# Analog_Sensors_Sheet.net
KiCad netlist of a schematic drawn in Altium Designer
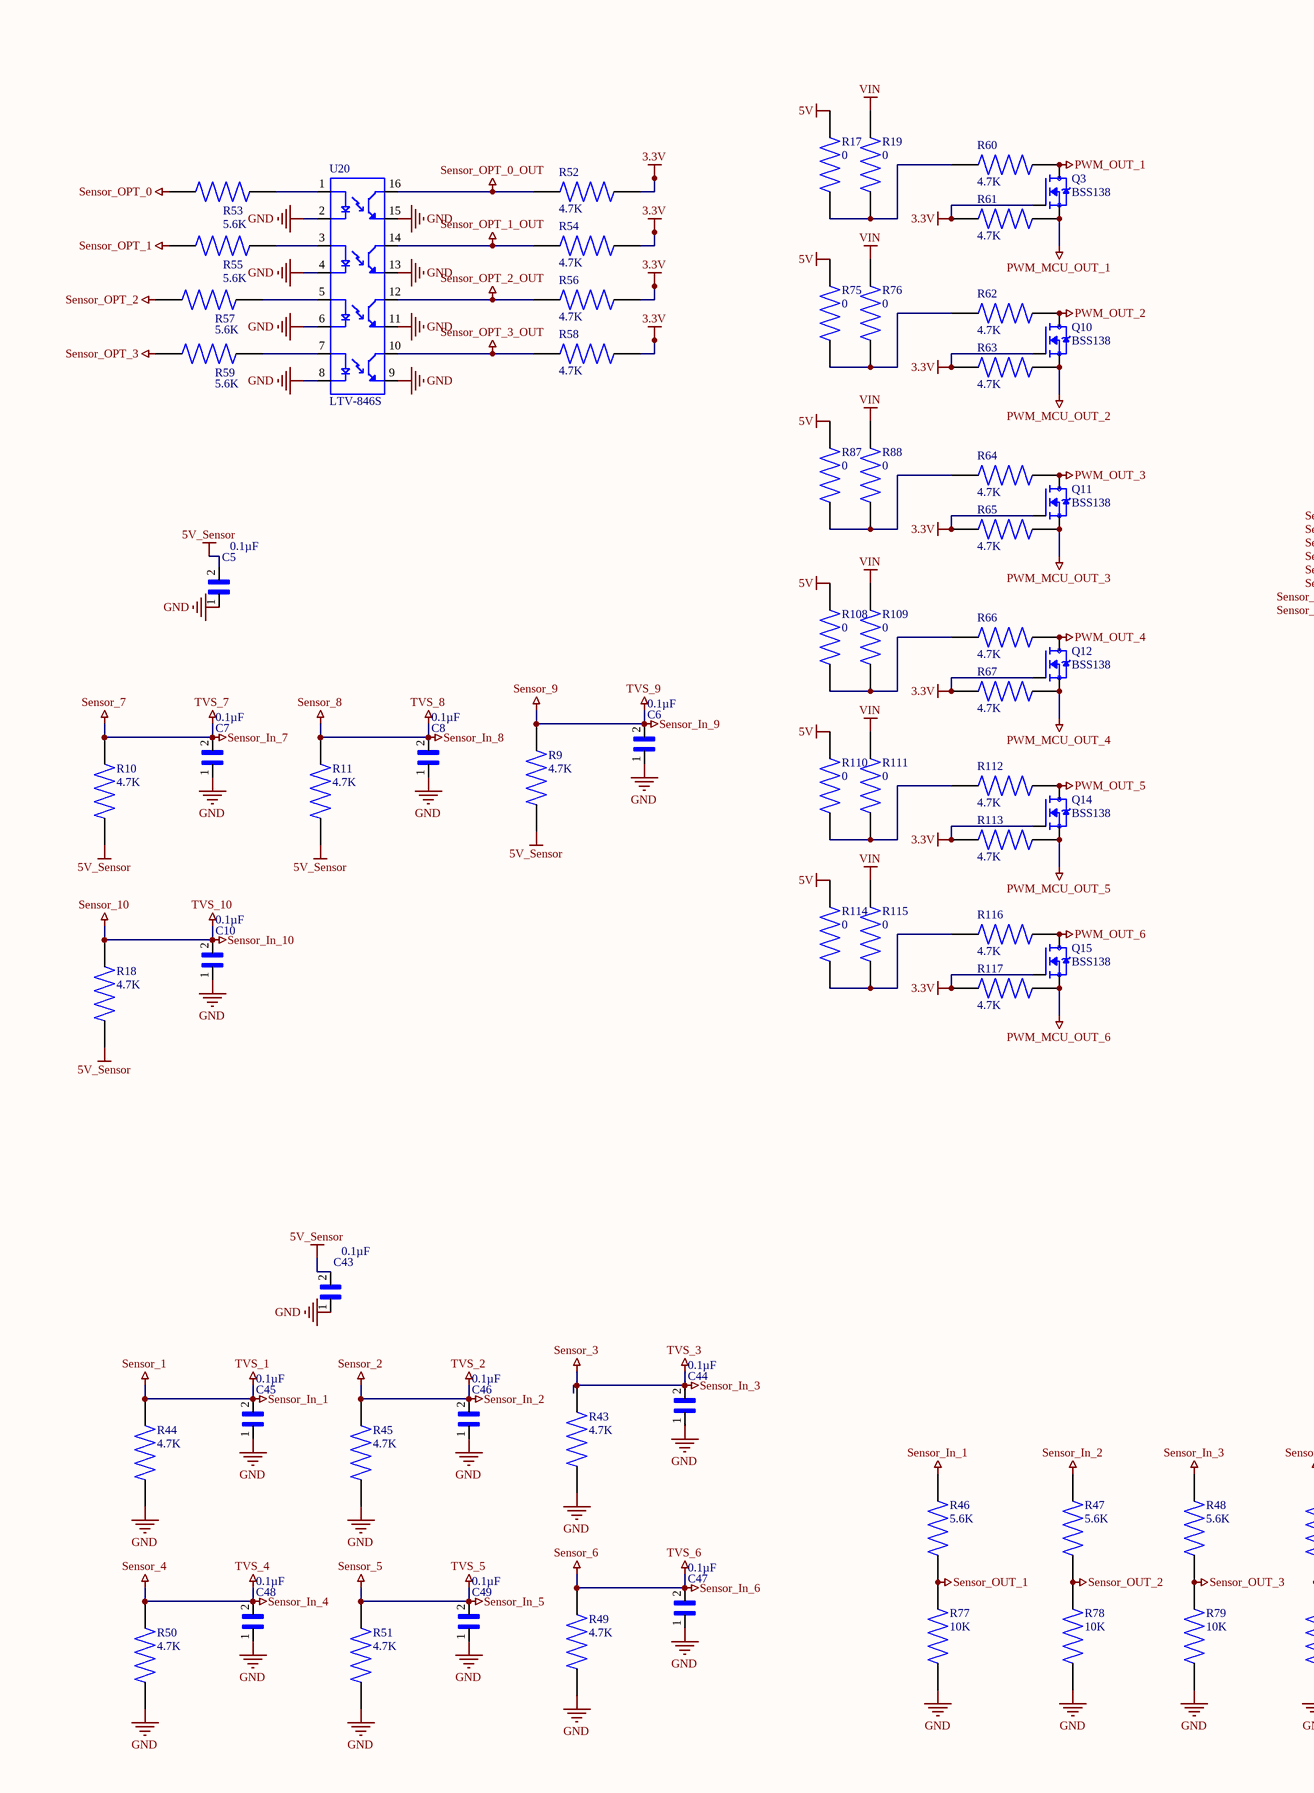
[diagram p0: Analog_Sensors_Sheet.SchDoc, left]
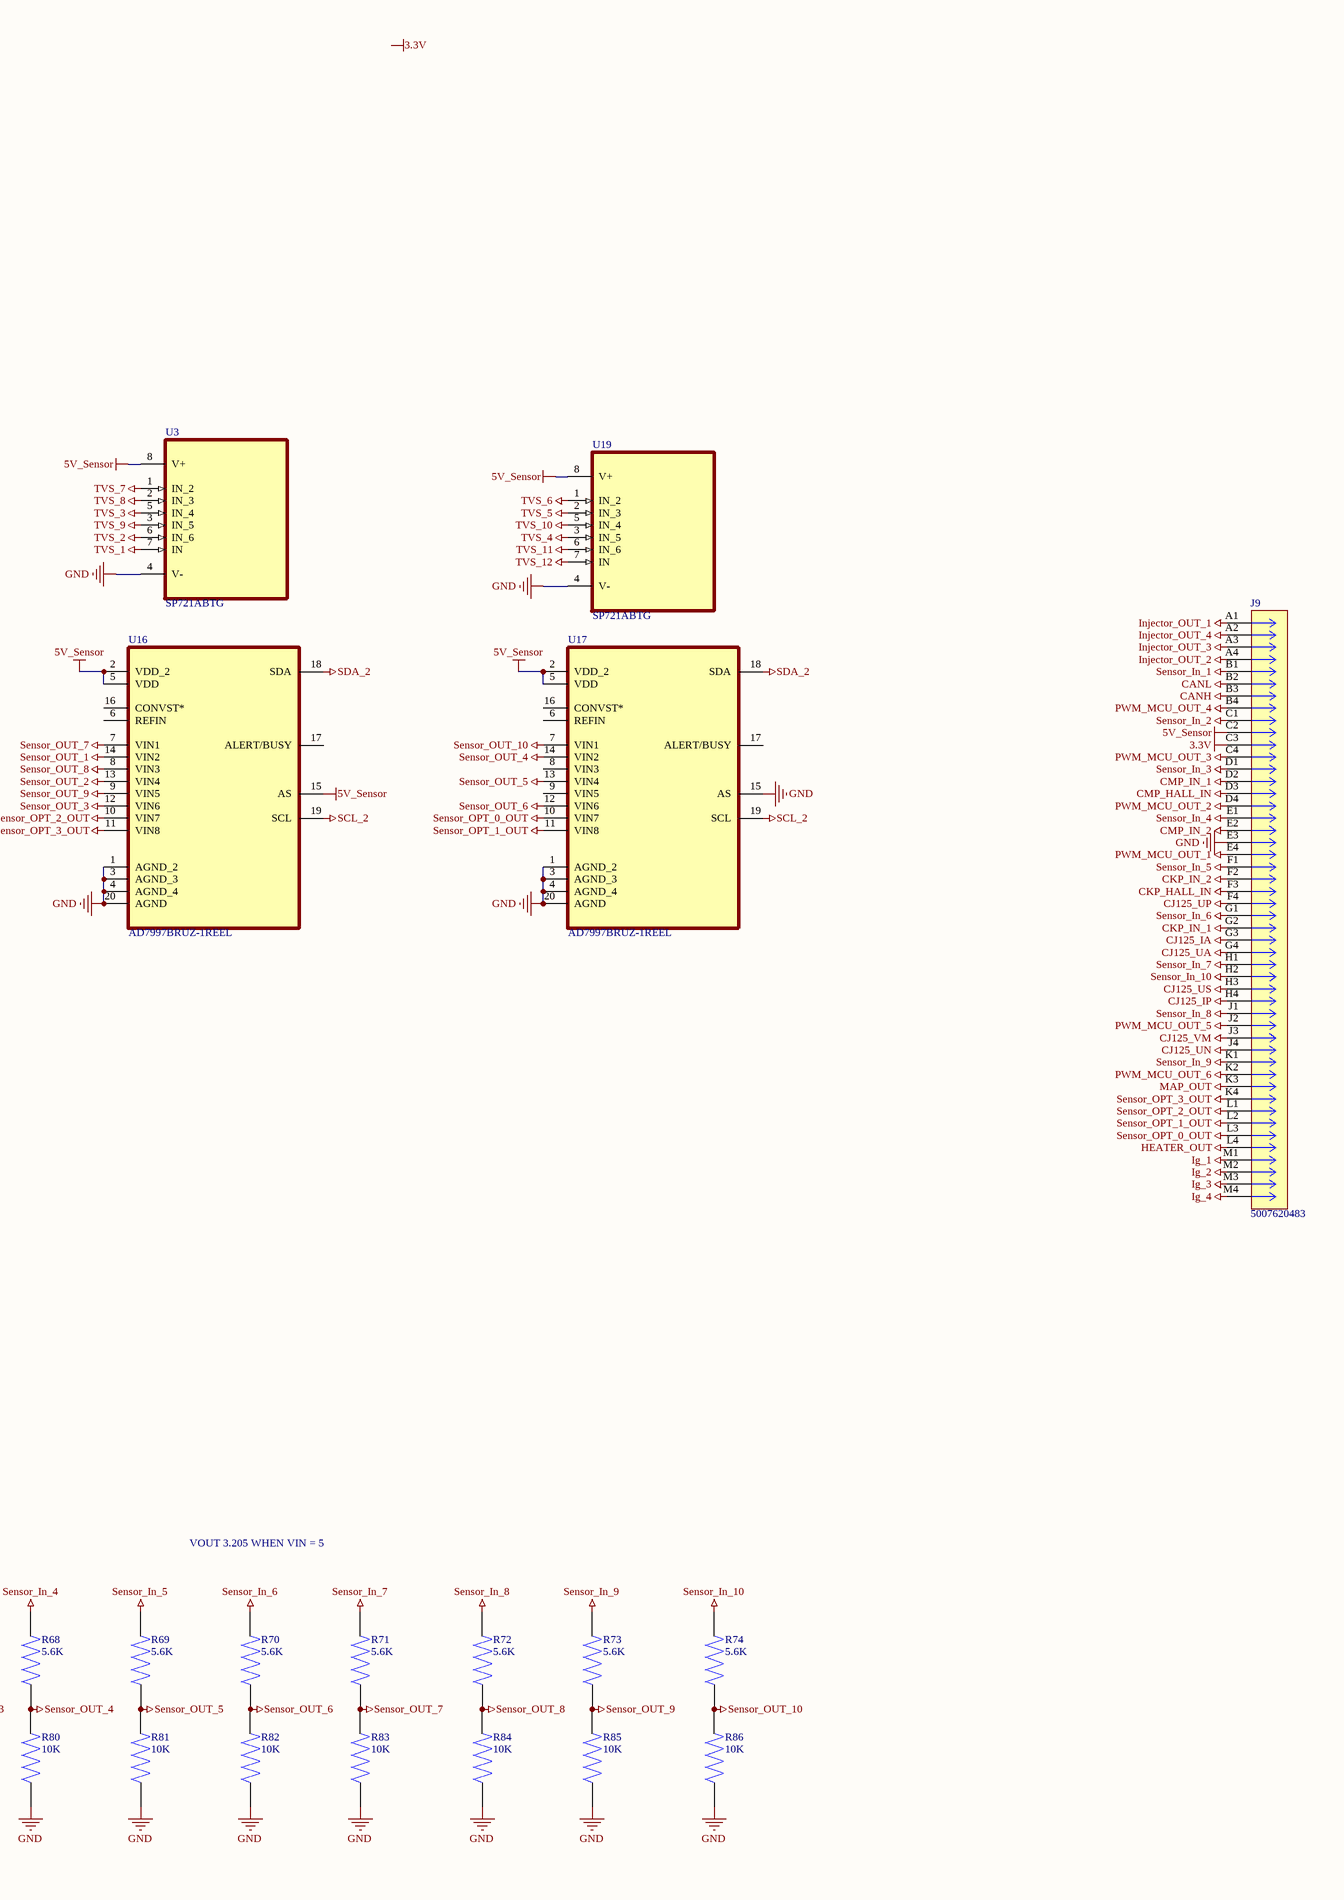
[diagram p1: Analog_Sensors_Sheet.SchDoc, right]

(export (version "E")
  (design (tool "Eeschema 10.0.6"))
  (components
    (comp (ref "C5")
      (value "0.1µF")
      (footprint "CAPC1608X90N")
      (description "Multilayer Ceramic Capacitors MLCC - SMD/SMT")
      (fields (field (name "MP") "06035C104MAZ2A"))
      (libsource (lib "06035C104MAZ2A") (part "06035C104MAZ2A"))
    )
    (comp (ref "C6")
      (value "0.1µF")
      (footprint "CAPC1608X90N")
      (description "Multilayer Ceramic Capacitors MLCC - SMD/SMT")
      (fields (field (name "MP") "06035C104MAZ2A"))
      (libsource (lib "06035C104MAZ2A") (part "06035C104MAZ2A"))
    )
    (comp (ref "C7")
      (value "0.1µF")
      (footprint "CAPC1608X90N")
      (description "Multilayer Ceramic Capacitors MLCC - SMD/SMT")
      (fields (field (name "MP") "06035C104MAZ2A"))
      (libsource (lib "06035C104MAZ2A") (part "06035C104MAZ2A"))
    )
    (comp (ref "C8")
      (value "0.1µF")
      (footprint "CAPC1608X90N")
      (description "Multilayer Ceramic Capacitors MLCC - SMD/SMT")
      (fields (field (name "MP") "06035C104MAZ2A"))
      (libsource (lib "06035C104MAZ2A") (part "06035C104MAZ2A"))
    )
    (comp (ref "C10")
      (value "0.1µF")
      (footprint "CAPC1608X90N")
      (description "Multilayer Ceramic Capacitors MLCC - SMD/SMT")
      (fields (field (name "MP") "06035C104MAZ2A"))
      (libsource (lib "06035C104MAZ2A") (part "06035C104MAZ2A"))
    )
    (comp (ref "C43")
      (value "0.1µF")
      (footprint "CAPC1608X90N")
      (description "Multilayer Ceramic Capacitors MLCC - SMD/SMT")
      (fields (field (name "MP") "06035C104MAZ2A"))
      (libsource (lib "06035C104MAZ2A") (part "06035C104MAZ2A"))
    )
    (comp (ref "C44")
      (value "0.1µF")
      (footprint "CAPC1608X90N")
      (description "Multilayer Ceramic Capacitors MLCC - SMD/SMT")
      (fields (field (name "MP") "06035C104MAZ2A"))
      (libsource (lib "06035C104MAZ2A") (part "06035C104MAZ2A"))
    )
    (comp (ref "C45")
      (value "0.1µF")
      (footprint "CAPC1608X90N")
      (description "Multilayer Ceramic Capacitors MLCC - SMD/SMT")
      (fields (field (name "MP") "06035C104MAZ2A"))
      (libsource (lib "06035C104MAZ2A") (part "06035C104MAZ2A"))
    )
    (comp (ref "C46")
      (value "0.1µF")
      (footprint "CAPC1608X90N")
      (description "Multilayer Ceramic Capacitors MLCC - SMD/SMT")
      (fields (field (name "MP") "06035C104MAZ2A"))
      (libsource (lib "06035C104MAZ2A") (part "06035C104MAZ2A"))
    )
    (comp (ref "C47")
      (value "0.1µF")
      (footprint "CAPC1608X90N")
      (description "Multilayer Ceramic Capacitors MLCC - SMD/SMT")
      (fields (field (name "MP") "06035C104MAZ2A"))
      (libsource (lib "06035C104MAZ2A") (part "06035C104MAZ2A"))
    )
    (comp (ref "C48")
      (value "0.1µF")
      (footprint "CAPC1608X90N")
      (description "Multilayer Ceramic Capacitors MLCC - SMD/SMT")
      (fields (field (name "MP") "06035C104MAZ2A"))
      (libsource (lib "06035C104MAZ2A") (part "06035C104MAZ2A"))
    )
    (comp (ref "C49")
      (value "0.1µF")
      (footprint "CAPC1608X90N")
      (description "Multilayer Ceramic Capacitors MLCC - SMD/SMT")
      (fields (field (name "MP") "06035C104MAZ2A"))
      (libsource (lib "06035C104MAZ2A") (part "06035C104MAZ2A"))
    )
    (comp (ref "J9")
      (value "5007620483")
      (footprint "CONN_SD-500762-001_MOL")
      (libsource (lib "5007620483") (part "5007620483"))
    )
    (comp (ref "Q3")
      (value "BSS138")
      (footprint "SOT95P240X111-3N")
      (description "N-Channel 50 V 220mA (Ta) 350mW (Ta) Surface Mount SOT-23-3")
      (fields (field (name "MF") "onsemi"))
      (libsource (lib "BSS138") (part "BSS138"))
    )
    (comp (ref "Q10")
      (value "BSS138")
      (footprint "SOT95P240X111-3N")
      (description "N-Channel 50 V 220mA (Ta) 350mW (Ta) Surface Mount SOT-23-3")
      (fields (field (name "MF") "onsemi"))
      (libsource (lib "BSS138") (part "BSS138"))
    )
    (comp (ref "Q11")
      (value "BSS138")
      (footprint "SOT95P240X111-3N")
      (description "N-Channel 50 V 220mA (Ta) 350mW (Ta) Surface Mount SOT-23-3")
      (fields (field (name "MF") "onsemi"))
      (libsource (lib "BSS138") (part "BSS138"))
    )
    (comp (ref "Q12")
      (value "BSS138")
      (footprint "SOT95P240X111-3N")
      (description "N-Channel 50 V 220mA (Ta) 350mW (Ta) Surface Mount SOT-23-3")
      (fields (field (name "MF") "onsemi"))
      (libsource (lib "BSS138") (part "BSS138"))
    )
    (comp (ref "Q14")
      (value "BSS138")
      (footprint "SOT95P240X111-3N")
      (description "N-Channel 50 V 220mA (Ta) 350mW (Ta) Surface Mount SOT-23-3")
      (fields (field (name "MF") "onsemi"))
      (libsource (lib "BSS138") (part "BSS138"))
    )
    (comp (ref "Q15")
      (value "BSS138")
      (footprint "SOT95P240X111-3N")
      (description "N-Channel 50 V 220mA (Ta) 350mW (Ta) Surface Mount SOT-23-3")
      (fields (field (name "MF") "onsemi"))
      (libsource (lib "BSS138") (part "BSS138"))
    )
    (comp (ref "R9")
      (value "4.7K")
      (footprint "RESC3116X65N")
      (description "4.7 kOhms Â±1% 0.25W, 1/4W Chip Resistor 1206 (3216 Metric) Moisture Resistant Thick Film")
      (fields (field (name "MF") "Yageo") (field (name "MP") "RC1206FR-074K7L"))
      (libsource (lib "RC1206FR-074K7L") (part "RC1206FR-074K7L"))
    )
    (comp (ref "R10")
      (value "4.7K")
      (footprint "RESC3116X65N")
      (description "4.7 kOhms Â±1% 0.25W, 1/4W Chip Resistor 1206 (3216 Metric) Moisture Resistant Thick Film")
      (fields (field (name "MF") "Yageo") (field (name "MP") "RC1206FR-074K7L"))
      (libsource (lib "RC1206FR-074K7L") (part "RC1206FR-074K7L"))
    )
    (comp (ref "R11")
      (value "4.7K")
      (footprint "RESC3116X65N")
      (description "4.7 kOhms Â±1% 0.25W, 1/4W Chip Resistor 1206 (3216 Metric) Moisture Resistant Thick Film")
      (fields (field (name "MF") "Yageo") (field (name "MP") "RC1206FR-074K7L"))
      (libsource (lib "RC1206FR-074K7L") (part "RC1206FR-074K7L"))
    )
    (comp (ref "R17")
      (value "0")
      (footprint "RESC3116X65N")
      (description "4.7 kOhms Â±1% 0.25W, 1/4W Chip Resistor 1206 (3216 Metric) Moisture Resistant Thick Film")
      (fields (field (name "MF") "Yageo") (field (name "MP") "RC1206FR-074K7L"))
      (libsource (lib "RC1206FR-074K7L") (part "RC1206FR-074K7L"))
    )
    (comp (ref "R18")
      (value "4.7K")
      (footprint "RESC3116X65N")
      (description "4.7 kOhms Â±1% 0.25W, 1/4W Chip Resistor 1206 (3216 Metric) Moisture Resistant Thick Film")
      (fields (field (name "MF") "Yageo") (field (name "MP") "RC1206FR-074K7L"))
      (libsource (lib "RC1206FR-074K7L") (part "RC1206FR-074K7L"))
    )
    (comp (ref "R19")
      (value "0")
      (footprint "RESC3116X65N")
      (description "4.7 kOhms Â±1% 0.25W, 1/4W Chip Resistor 1206 (3216 Metric) Moisture Resistant Thick Film")
      (fields (field (name "MF") "Yageo") (field (name "MP") "RC1206FR-074K7L"))
      (libsource (lib "RC1206FR-074K7L") (part "RC1206FR-074K7L"))
    )
    (comp (ref "R43")
      (value "4.7K")
      (footprint "RESC3116X65N")
      (description "4.7 kOhms Â±1% 0.25W, 1/4W Chip Resistor 1206 (3216 Metric) Moisture Resistant Thick Film")
      (fields (field (name "MF") "Yageo") (field (name "MP") "RC1206FR-074K7L"))
      (libsource (lib "RC1206FR-074K7L") (part "RC1206FR-074K7L"))
    )
    (comp (ref "R44")
      (value "4.7K")
      (footprint "RESC3116X65N")
      (description "4.7 kOhms Â±1% 0.25W, 1/4W Chip Resistor 1206 (3216 Metric) Moisture Resistant Thick Film")
      (fields (field (name "MF") "Yageo") (field (name "MP") "RC1206FR-074K7L"))
      (libsource (lib "RC1206FR-074K7L") (part "RC1206FR-074K7L"))
    )
    (comp (ref "R45")
      (value "4.7K")
      (footprint "RESC3116X65N")
      (description "4.7 kOhms Â±1% 0.25W, 1/4W Chip Resistor 1206 (3216 Metric) Moisture Resistant Thick Film")
      (fields (field (name "MF") "Yageo") (field (name "MP") "RC1206FR-074K7L"))
      (libsource (lib "RC1206FR-074K7L") (part "RC1206FR-074K7L"))
    )
    (comp (ref "R46")
      (value "5.6K")
      (footprint "RESC3116X65N")
      (fields (field (name "MP") "AA1206JR-07470RL"))
      (libsource (lib "AA1206JR-07470RL") (part "AA1206JR-07470RL"))
    )
    (comp (ref "R47")
      (value "5.6K")
      (footprint "RESC3116X65N")
      (fields (field (name "MP") "AA1206JR-07470RL"))
      (libsource (lib "AA1206JR-07470RL") (part "AA1206JR-07470RL"))
    )
    (comp (ref "R48")
      (value "5.6K")
      (footprint "RESC3116X65N")
      (fields (field (name "MP") "AA1206JR-07470RL"))
      (libsource (lib "AA1206JR-07470RL") (part "AA1206JR-07470RL"))
    )
    (comp (ref "R49")
      (value "4.7K")
      (footprint "RESC3116X65N")
      (description "4.7 kOhms Â±1% 0.25W, 1/4W Chip Resistor 1206 (3216 Metric) Moisture Resistant Thick Film")
      (fields (field (name "MF") "Yageo") (field (name "MP") "RC1206FR-074K7L"))
      (libsource (lib "RC1206FR-074K7L") (part "RC1206FR-074K7L"))
    )
    (comp (ref "R50")
      (value "4.7K")
      (footprint "RESC3116X65N")
      (description "4.7 kOhms Â±1% 0.25W, 1/4W Chip Resistor 1206 (3216 Metric) Moisture Resistant Thick Film")
      (fields (field (name "MF") "Yageo") (field (name "MP") "RC1206FR-074K7L"))
      (libsource (lib "RC1206FR-074K7L") (part "RC1206FR-074K7L"))
    )
    (comp (ref "R51")
      (value "4.7K")
      (footprint "RESC3116X65N")
      (description "4.7 kOhms Â±1% 0.25W, 1/4W Chip Resistor 1206 (3216 Metric) Moisture Resistant Thick Film")
      (fields (field (name "MF") "Yageo") (field (name "MP") "RC1206FR-074K7L"))
      (libsource (lib "RC1206FR-074K7L") (part "RC1206FR-074K7L"))
    )
    (comp (ref "R52")
      (value "4.7K")
      (footprint "RES_ERJS06J472V")
      (fields (field (name "MP") "ERJS06J472V"))
      (libsource (lib "ERJS06J472V") (part "ERJS06J472V"))
    )
    (comp (ref "R53")
      (value "5.6K")
      (footprint "RESC3216X70N")
      (description "Res Thick Film 1206 220 Ohm 1% 0.25W(1/4W) ?100ppm/?C SMD Automotive T/R")
      (fields (field (name "MP") "RK73H2BTTD2200F"))
      (libsource (lib "RK73H2BTTD2200F") (part "RK73H2BTTD2200F"))
    )
    (comp (ref "R54")
      (value "4.7K")
      (footprint "RES_ERJS06J472V")
      (fields (field (name "MP") "ERJS06J472V"))
      (libsource (lib "ERJS06J472V") (part "ERJS06J472V"))
    )
    (comp (ref "R55")
      (value "5.6K")
      (footprint "RESC3216X70N")
      (description "Res Thick Film 1206 220 Ohm 1% 0.25W(1/4W) ?100ppm/?C SMD Automotive T/R")
      (fields (field (name "MP") "RK73H2BTTD2200F"))
      (libsource (lib "RK73H2BTTD2200F") (part "RK73H2BTTD2200F"))
    )
    (comp (ref "R56")
      (value "4.7K")
      (footprint "RES_ERJS06J472V")
      (fields (field (name "MP") "ERJS06J472V"))
      (libsource (lib "ERJS06J472V") (part "ERJS06J472V"))
    )
    (comp (ref "R57")
      (value "5.6K")
      (footprint "RESC3216X70N")
      (description "Res Thick Film 1206 220 Ohm 1% 0.25W(1/4W) ?100ppm/?C SMD Automotive T/R")
      (fields (field (name "MP") "RK73H2BTTD2200F"))
      (libsource (lib "RK73H2BTTD2200F") (part "RK73H2BTTD2200F"))
    )
    (comp (ref "R58")
      (value "4.7K")
      (footprint "RES_ERJS06J472V")
      (fields (field (name "MP") "ERJS06J472V"))
      (libsource (lib "ERJS06J472V") (part "ERJS06J472V"))
    )
    (comp (ref "R59")
      (value "5.6K")
      (footprint "RESC3216X70N")
      (description "Res Thick Film 1206 220 Ohm 1% 0.25W(1/4W) ?100ppm/?C SMD Automotive T/R")
      (fields (field (name "MP") "RK73H2BTTD2200F"))
      (libsource (lib "RK73H2BTTD2200F") (part "RK73H2BTTD2200F"))
    )
    (comp (ref "R60")
      (value "4.7K")
      (footprint "RESC3116X65N")
      (description "4.7 kOhms Â±1% 0.25W, 1/4W Chip Resistor 1206 (3216 Metric) Moisture Resistant Thick Film")
      (fields (field (name "MF") "Yageo") (field (name "MP") "RC1206FR-074K7L"))
      (libsource (lib "RC1206FR-074K7L") (part "RC1206FR-074K7L"))
    )
    (comp (ref "R61")
      (value "4.7K")
      (footprint "RESC3116X65N")
      (description "4.7 kOhms Â±1% 0.25W, 1/4W Chip Resistor 1206 (3216 Metric) Moisture Resistant Thick Film")
      (fields (field (name "MF") "Yageo") (field (name "MP") "RC1206FR-074K7L"))
      (libsource (lib "RC1206FR-074K7L") (part "RC1206FR-074K7L"))
    )
    (comp (ref "R62")
      (value "4.7K")
      (footprint "RESC3116X65N")
      (description "4.7 kOhms Â±1% 0.25W, 1/4W Chip Resistor 1206 (3216 Metric) Moisture Resistant Thick Film")
      (fields (field (name "MF") "Yageo") (field (name "MP") "RC1206FR-074K7L"))
      (libsource (lib "RC1206FR-074K7L") (part "RC1206FR-074K7L"))
    )
    (comp (ref "R63")
      (value "4.7K")
      (footprint "RESC3116X65N")
      (description "4.7 kOhms Â±1% 0.25W, 1/4W Chip Resistor 1206 (3216 Metric) Moisture Resistant Thick Film")
      (fields (field (name "MF") "Yageo") (field (name "MP") "RC1206FR-074K7L"))
      (libsource (lib "RC1206FR-074K7L") (part "RC1206FR-074K7L"))
    )
    (comp (ref "R64")
      (value "4.7K")
      (footprint "RESC3116X65N")
      (description "4.7 kOhms Â±1% 0.25W, 1/4W Chip Resistor 1206 (3216 Metric) Moisture Resistant Thick Film")
      (fields (field (name "MF") "Yageo") (field (name "MP") "RC1206FR-074K7L"))
      (libsource (lib "RC1206FR-074K7L") (part "RC1206FR-074K7L"))
    )
    (comp (ref "R65")
      (value "4.7K")
      (footprint "RESC3116X65N")
      (description "4.7 kOhms Â±1% 0.25W, 1/4W Chip Resistor 1206 (3216 Metric) Moisture Resistant Thick Film")
      (fields (field (name "MF") "Yageo") (field (name "MP") "RC1206FR-074K7L"))
      (libsource (lib "RC1206FR-074K7L") (part "RC1206FR-074K7L"))
    )
    (comp (ref "R66")
      (value "4.7K")
      (footprint "RESC3116X65N")
      (description "4.7 kOhms Â±1% 0.25W, 1/4W Chip Resistor 1206 (3216 Metric) Moisture Resistant Thick Film")
      (fields (field (name "MF") "Yageo") (field (name "MP") "RC1206FR-074K7L"))
      (libsource (lib "RC1206FR-074K7L") (part "RC1206FR-074K7L"))
    )
    (comp (ref "R67")
      (value "4.7K")
      (footprint "RESC3116X65N")
      (description "4.7 kOhms Â±1% 0.25W, 1/4W Chip Resistor 1206 (3216 Metric) Moisture Resistant Thick Film")
      (fields (field (name "MF") "Yageo") (field (name "MP") "RC1206FR-074K7L"))
      (libsource (lib "RC1206FR-074K7L") (part "RC1206FR-074K7L"))
    )
    (comp (ref "R68")
      (value "5.6K")
      (footprint "RESC3116X65N")
      (fields (field (name "MP") "AA1206JR-07470RL"))
      (libsource (lib "AA1206JR-07470RL") (part "AA1206JR-07470RL"))
    )
    (comp (ref "R69")
      (value "5.6K")
      (footprint "RESC3116X65N")
      (fields (field (name "MP") "AA1206JR-07470RL"))
      (libsource (lib "AA1206JR-07470RL") (part "AA1206JR-07470RL"))
    )
    (comp (ref "R70")
      (value "5.6K")
      (footprint "RESC3116X65N")
      (fields (field (name "MP") "AA1206JR-07470RL"))
      (libsource (lib "AA1206JR-07470RL") (part "AA1206JR-07470RL"))
    )
    (comp (ref "R71")
      (value "5.6K")
      (footprint "RESC3116X65N")
      (fields (field (name "MP") "AA1206JR-07470RL"))
      (libsource (lib "AA1206JR-07470RL") (part "AA1206JR-07470RL"))
    )
    (comp (ref "R72")
      (value "5.6K")
      (footprint "RESC3116X65N")
      (fields (field (name "MP") "AA1206JR-07470RL"))
      (libsource (lib "AA1206JR-07470RL") (part "AA1206JR-07470RL"))
    )
    (comp (ref "R73")
      (value "5.6K")
      (footprint "RESC3116X65N")
      (fields (field (name "MP") "AA1206JR-07470RL"))
      (libsource (lib "AA1206JR-07470RL") (part "AA1206JR-07470RL"))
    )
    (comp (ref "R74")
      (value "5.6K")
      (footprint "RESC3116X65N")
      (fields (field (name "MP") "AA1206JR-07470RL"))
      (libsource (lib "AA1206JR-07470RL") (part "AA1206JR-07470RL"))
    )
    (comp (ref "R75")
      (value "0")
      (footprint "RESC3116X65N")
      (description "4.7 kOhms Â±1% 0.25W, 1/4W Chip Resistor 1206 (3216 Metric) Moisture Resistant Thick Film")
      (fields (field (name "MF") "Yageo") (field (name "MP") "RC1206FR-074K7L"))
      (libsource (lib "RC1206FR-074K7L") (part "RC1206FR-074K7L"))
    )
    (comp (ref "R76")
      (value "0")
      (footprint "RESC3116X65N")
      (description "4.7 kOhms Â±1% 0.25W, 1/4W Chip Resistor 1206 (3216 Metric) Moisture Resistant Thick Film")
      (fields (field (name "MF") "Yageo") (field (name "MP") "RC1206FR-074K7L"))
      (libsource (lib "RC1206FR-074K7L") (part "RC1206FR-074K7L"))
    )
    (comp (ref "R77")
      (value "10K")
      (footprint "RESC3116X65N")
      (fields (field (name "MP") "AA1206JR-07470RL"))
      (libsource (lib "AA1206JR-07470RL") (part "AA1206JR-07470RL"))
    )
    (comp (ref "R78")
      (value "10K")
      (footprint "RESC3116X65N")
      (fields (field (name "MP") "AA1206JR-07470RL"))
      (libsource (lib "AA1206JR-07470RL") (part "AA1206JR-07470RL"))
    )
    (comp (ref "R79")
      (value "10K")
      (footprint "RESC3116X65N")
      (fields (field (name "MP") "AA1206JR-07470RL"))
      (libsource (lib "AA1206JR-07470RL") (part "AA1206JR-07470RL"))
    )
    (comp (ref "R80")
      (value "10K")
      (footprint "RESC3116X65N")
      (fields (field (name "MP") "AA1206JR-07470RL"))
      (libsource (lib "AA1206JR-07470RL") (part "AA1206JR-07470RL"))
    )
    (comp (ref "R81")
      (value "10K")
      (footprint "RESC3116X65N")
      (fields (field (name "MP") "AA1206JR-07470RL"))
      (libsource (lib "AA1206JR-07470RL") (part "AA1206JR-07470RL"))
    )
    (comp (ref "R82")
      (value "10K")
      (footprint "RESC3116X65N")
      (fields (field (name "MP") "AA1206JR-07470RL"))
      (libsource (lib "AA1206JR-07470RL") (part "AA1206JR-07470RL"))
    )
    (comp (ref "R83")
      (value "10K")
      (footprint "RESC3116X65N")
      (fields (field (name "MP") "AA1206JR-07470RL"))
      (libsource (lib "AA1206JR-07470RL") (part "AA1206JR-07470RL"))
    )
    (comp (ref "R84")
      (value "10K")
      (footprint "RESC3116X65N")
      (fields (field (name "MP") "AA1206JR-07470RL"))
      (libsource (lib "AA1206JR-07470RL") (part "AA1206JR-07470RL"))
    )
    (comp (ref "R85")
      (value "10K")
      (footprint "RESC3116X65N")
      (fields (field (name "MP") "AA1206JR-07470RL"))
      (libsource (lib "AA1206JR-07470RL") (part "AA1206JR-07470RL"))
    )
    (comp (ref "R86")
      (value "10K")
      (footprint "RESC3116X65N")
      (fields (field (name "MP") "AA1206JR-07470RL"))
      (libsource (lib "AA1206JR-07470RL") (part "AA1206JR-07470RL"))
    )
    (comp (ref "R87")
      (value "0")
      (footprint "RESC3116X65N")
      (description "4.7 kOhms Â±1% 0.25W, 1/4W Chip Resistor 1206 (3216 Metric) Moisture Resistant Thick Film")
      (fields (field (name "MF") "Yageo") (field (name "MP") "RC1206FR-074K7L"))
      (libsource (lib "RC1206FR-074K7L") (part "RC1206FR-074K7L"))
    )
    (comp (ref "R88")
      (value "0")
      (footprint "RESC3116X65N")
      (description "4.7 kOhms Â±1% 0.25W, 1/4W Chip Resistor 1206 (3216 Metric) Moisture Resistant Thick Film")
      (fields (field (name "MF") "Yageo") (field (name "MP") "RC1206FR-074K7L"))
      (libsource (lib "RC1206FR-074K7L") (part "RC1206FR-074K7L"))
    )
    (comp (ref "R108")
      (value "0")
      (footprint "RESC3116X65N")
      (description "4.7 kOhms Â±1% 0.25W, 1/4W Chip Resistor 1206 (3216 Metric) Moisture Resistant Thick Film")
      (fields (field (name "MF") "Yageo") (field (name "MP") "RC1206FR-074K7L"))
      (libsource (lib "RC1206FR-074K7L") (part "RC1206FR-074K7L"))
    )
    (comp (ref "R109")
      (value "0")
      (footprint "RESC3116X65N")
      (description "4.7 kOhms Â±1% 0.25W, 1/4W Chip Resistor 1206 (3216 Metric) Moisture Resistant Thick Film")
      (fields (field (name "MF") "Yageo") (field (name "MP") "RC1206FR-074K7L"))
      (libsource (lib "RC1206FR-074K7L") (part "RC1206FR-074K7L"))
    )
    (comp (ref "R110")
      (value "0")
      (footprint "RESC3116X65N")
      (description "4.7 kOhms Â±1% 0.25W, 1/4W Chip Resistor 1206 (3216 Metric) Moisture Resistant Thick Film")
      (fields (field (name "MF") "Yageo") (field (name "MP") "RC1206FR-074K7L"))
      (libsource (lib "RC1206FR-074K7L") (part "RC1206FR-074K7L"))
    )
    (comp (ref "R111")
      (value "0")
      (footprint "RESC3116X65N")
      (description "4.7 kOhms Â±1% 0.25W, 1/4W Chip Resistor 1206 (3216 Metric) Moisture Resistant Thick Film")
      (fields (field (name "MF") "Yageo") (field (name "MP") "RC1206FR-074K7L"))
      (libsource (lib "RC1206FR-074K7L") (part "RC1206FR-074K7L"))
    )
    (comp (ref "R112")
      (value "4.7K")
      (footprint "RESC3116X65N")
      (description "4.7 kOhms Â±1% 0.25W, 1/4W Chip Resistor 1206 (3216 Metric) Moisture Resistant Thick Film")
      (fields (field (name "MF") "Yageo") (field (name "MP") "RC1206FR-074K7L"))
      (libsource (lib "RC1206FR-074K7L") (part "RC1206FR-074K7L"))
    )
    (comp (ref "R113")
      (value "4.7K")
      (footprint "RESC3116X65N")
      (description "4.7 kOhms Â±1% 0.25W, 1/4W Chip Resistor 1206 (3216 Metric) Moisture Resistant Thick Film")
      (fields (field (name "MF") "Yageo") (field (name "MP") "RC1206FR-074K7L"))
      (libsource (lib "RC1206FR-074K7L") (part "RC1206FR-074K7L"))
    )
    (comp (ref "R114")
      (value "0")
      (footprint "RESC3116X65N")
      (description "4.7 kOhms Â±1% 0.25W, 1/4W Chip Resistor 1206 (3216 Metric) Moisture Resistant Thick Film")
      (fields (field (name "MF") "Yageo") (field (name "MP") "RC1206FR-074K7L"))
      (libsource (lib "RC1206FR-074K7L") (part "RC1206FR-074K7L"))
    )
    (comp (ref "R115")
      (value "0")
      (footprint "RESC3116X65N")
      (description "4.7 kOhms Â±1% 0.25W, 1/4W Chip Resistor 1206 (3216 Metric) Moisture Resistant Thick Film")
      (fields (field (name "MF") "Yageo") (field (name "MP") "RC1206FR-074K7L"))
      (libsource (lib "RC1206FR-074K7L") (part "RC1206FR-074K7L"))
    )
    (comp (ref "R116")
      (value "4.7K")
      (footprint "RESC3116X65N")
      (description "4.7 kOhms Â±1% 0.25W, 1/4W Chip Resistor 1206 (3216 Metric) Moisture Resistant Thick Film")
      (fields (field (name "MF") "Yageo") (field (name "MP") "RC1206FR-074K7L"))
      (libsource (lib "RC1206FR-074K7L") (part "RC1206FR-074K7L"))
    )
    (comp (ref "R117")
      (value "4.7K")
      (footprint "RESC3116X65N")
      (description "4.7 kOhms Â±1% 0.25W, 1/4W Chip Resistor 1206 (3216 Metric) Moisture Resistant Thick Film")
      (fields (field (name "MF") "Yageo") (field (name "MP") "RC1206FR-074K7L"))
      (libsource (lib "RC1206FR-074K7L") (part "RC1206FR-074K7L"))
    )
    (comp (ref "U3")
      (value "SP721ABTG")
      (footprint "SOIC127P600X175-8N")
      (description "TVS Diode Arrays")
      (libsource (lib "SP721ABTG") (part "SP721ABTG"))
    )
    (comp (ref "U16")
      (value "AD7997BRUZ-1REEL")
      (footprint "SOP65P640X120-20N")
      (fields (field (name "MF") "Analog Devices") (field (name "MP") "AD7997BRUZ1"))
      (libsource (lib "AD7997BRUZ-1REEL") (part "AD7997BRUZ-1REEL"))
    )
    (comp (ref "U17")
      (value "AD7997BRUZ-1REEL")
      (footprint "SOP65P640X120-20N")
      (fields (field (name "MF") "Analog Devices") (field (name "MP") "AD7997BRUZ1"))
      (libsource (lib "AD7997BRUZ-1REEL") (part "AD7997BRUZ-1REEL"))
    )
    (comp (ref "U19")
      (value "SP721ABTG")
      (footprint "SOIC127P600X175-8N")
      (description "TVS Diode Arrays")
      (libsource (lib "SP721ABTG") (part "SP721ABTG"))
    )
    (comp (ref "U20")
      (value "LTV-846S")
      (footprint "SOIC254P1016X460-16N")
      (description "Optoisolator Transistor Output 5000Vrms 4 Channel 16-SMD")
      (fields (field (name "MF") "Lite-On Inc.") (field (name "DIGI-KEY_PART_NUMBER") "160-1365-5-ND"))
      (libsource (lib "LTV-846S") (part "LTV-846S"))
    )
  )
  (nets
    (net (code "1") (name "3.3V") (class "Default")
      (node (ref "J9") (pin "C3") (pinfunction "C3_C3") (pintype "passive"))
      (node (ref "Q10") (pin "1") (pinfunction "G_1") (pintype "passive"))
      (node (ref "Q11") (pin "1") (pinfunction "G_1") (pintype "passive"))
      (node (ref "Q12") (pin "1") (pinfunction "G_1") (pintype "passive"))
      (node (ref "Q14") (pin "1") (pinfunction "G_1") (pintype "passive"))
      (node (ref "Q15") (pin "1") (pinfunction "G_1") (pintype "passive"))
      (node (ref "Q3") (pin "1") (pinfunction "G_1") (pintype "passive"))
      (node (ref "R113") (pin "2") (pinfunction "2_2") (pintype "passive"))
      (node (ref "R117") (pin "2") (pinfunction "2_2") (pintype "passive"))
      (node (ref "R52") (pin "2") (pinfunction "2_2") (pintype "passive"))
      (node (ref "R54") (pin "2") (pinfunction "2_2") (pintype "passive"))
      (node (ref "R56") (pin "2") (pinfunction "2_2") (pintype "passive"))
      (node (ref "R58") (pin "2") (pinfunction "2_2") (pintype "passive"))
      (node (ref "R61") (pin "2") (pinfunction "2_2") (pintype "passive"))
      (node (ref "R63") (pin "2") (pinfunction "2_2") (pintype "passive"))
      (node (ref "R65") (pin "2") (pinfunction "2_2") (pintype "passive"))
      (node (ref "R67") (pin "2") (pinfunction "2_2") (pintype "passive"))
    )
    (net (code "2") (name "5V") (class "Default")
      (node (ref "R108") (pin "2") (pinfunction "2_2") (pintype "passive"))
      (node (ref "R110") (pin "2") (pinfunction "2_2") (pintype "passive"))
      (node (ref "R114") (pin "2") (pinfunction "2_2") (pintype "passive"))
      (node (ref "R17") (pin "2") (pinfunction "2_2") (pintype "passive"))
      (node (ref "R75") (pin "2") (pinfunction "2_2") (pintype "passive"))
      (node (ref "R87") (pin "2") (pinfunction "2_2") (pintype "passive"))
    )
    (net (code "3") (name "5V_Sensor") (class "Default")
      (node (ref "C43") (pin "2") (pinfunction "2_2") (pintype "passive"))
      (node (ref "C5") (pin "2") (pinfunction "2_2") (pintype "passive"))
      (node (ref "J9") (pin "C2") (pinfunction "C2_C2") (pintype "passive"))
      (node (ref "R10") (pin "1") (pinfunction "1_1") (pintype "passive"))
      (node (ref "R11") (pin "1") (pinfunction "1_1") (pintype "passive"))
      (node (ref "R18") (pin "1") (pinfunction "1_1") (pintype "passive"))
      (node (ref "R9") (pin "1") (pinfunction "1_1") (pintype "passive"))
      (node (ref "U16") (pin "15") (pinfunction "AS_15") (pintype "passive"))
      (node (ref "U16") (pin "2") (pinfunction "VDD_2_2") (pintype "power_in"))
      (node (ref "U16") (pin "5") (pinfunction "VDD_5") (pintype "power_in"))
      (node (ref "U17") (pin "2") (pinfunction "VDD_2_2") (pintype "power_in"))
      (node (ref "U17") (pin "5") (pinfunction "VDD_5") (pintype "power_in"))
      (node (ref "U19") (pin "8") (pinfunction "V+_8") (pintype "power_in"))
      (node (ref "U3") (pin "8") (pinfunction "V+_8") (pintype "power_in"))
    )
    (net (code "4") (name "CANH") (class "Default")
      (node (ref "J9") (pin "B3") (pinfunction "B3_B3") (pintype "passive"))
    )
    (net (code "5") (name "CANL") (class "Default")
      (node (ref "J9") (pin "B2") (pinfunction "B2_B2") (pintype "passive"))
    )
    (net (code "6") (name "CJ125_IA") (class "Default")
      (node (ref "J9") (pin "G3") (pinfunction "G3_G3") (pintype "passive"))
    )
    (net (code "7") (name "CJ125_IP") (class "Default")
      (node (ref "J9") (pin "H4") (pinfunction "H4_H4") (pintype "passive"))
    )
    (net (code "8") (name "CJ125_UA") (class "Default")
      (node (ref "J9") (pin "G4") (pinfunction "G4_G4") (pintype "passive"))
    )
    (net (code "9") (name "CJ125_UN") (class "Default")
      (node (ref "J9") (pin "J4") (pinfunction "J4_J4") (pintype "passive"))
    )
    (net (code "10") (name "CJ125_UP") (class "Default")
      (node (ref "J9") (pin "F4") (pinfunction "F4_F4") (pintype "passive"))
    )
    (net (code "11") (name "CJ125_US") (class "Default")
      (node (ref "J9") (pin "H3") (pinfunction "H3_H3") (pintype "passive"))
    )
    (net (code "12") (name "CJ125_VM") (class "Default")
      (node (ref "J9") (pin "J3") (pinfunction "J3_J3") (pintype "passive"))
    )
    (net (code "13") (name "CKP_HALL_IN") (class "Default")
      (node (ref "J9") (pin "F3") (pinfunction "F3_F3") (pintype "passive"))
    )
    (net (code "14") (name "CKP_IN_1") (class "Default")
      (node (ref "J9") (pin "G2") (pinfunction "G2_G2") (pintype "passive"))
    )
    (net (code "15") (name "CKP_IN_2") (class "Default")
      (node (ref "J9") (pin "F2") (pinfunction "F2_F2") (pintype "passive"))
    )
    (net (code "16") (name "CMP_HALL_IN") (class "Default")
      (node (ref "J9") (pin "D3") (pinfunction "D3_D3") (pintype "passive"))
    )
    (net (code "17") (name "CMP_IN_1") (class "Default")
      (node (ref "J9") (pin "D2") (pinfunction "D2_D2") (pintype "passive"))
    )
    (net (code "18") (name "CMP_IN_2") (class "Default")
      (node (ref "J9") (pin "E2") (pinfunction "E2_E2") (pintype "passive"))
    )
    (net (code "19") (name "GND") (class "Default")
      (node (ref "C10") (pin "1") (pinfunction "1_1") (pintype "passive"))
      (node (ref "C43") (pin "1") (pinfunction "1_1") (pintype "passive"))
      (node (ref "C44") (pin "1") (pinfunction "1_1") (pintype "passive"))
      (node (ref "C45") (pin "1") (pinfunction "1_1") (pintype "passive"))
      (node (ref "C46") (pin "1") (pinfunction "1_1") (pintype "passive"))
      (node (ref "C47") (pin "1") (pinfunction "1_1") (pintype "passive"))
      (node (ref "C48") (pin "1") (pinfunction "1_1") (pintype "passive"))
      (node (ref "C49") (pin "1") (pinfunction "1_1") (pintype "passive"))
      (node (ref "C5") (pin "1") (pinfunction "1_1") (pintype "passive"))
      (node (ref "C6") (pin "1") (pinfunction "1_1") (pintype "passive"))
      (node (ref "C7") (pin "1") (pinfunction "1_1") (pintype "passive"))
      (node (ref "C8") (pin "1") (pinfunction "1_1") (pintype "passive"))
      (node (ref "J9") (pin "E3") (pinfunction "E3_E3") (pintype "passive"))
      (node (ref "R43") (pin "1") (pinfunction "1_1") (pintype "passive"))
      (node (ref "R44") (pin "1") (pinfunction "1_1") (pintype "passive"))
      (node (ref "R45") (pin "1") (pinfunction "1_1") (pintype "passive"))
      (node (ref "R49") (pin "1") (pinfunction "1_1") (pintype "passive"))
      (node (ref "R50") (pin "1") (pinfunction "1_1") (pintype "passive"))
      (node (ref "R51") (pin "1") (pinfunction "1_1") (pintype "passive"))
      (node (ref "R77") (pin "1") (pinfunction "1_1") (pintype "passive"))
      (node (ref "R78") (pin "1") (pinfunction "1_1") (pintype "passive"))
      (node (ref "R79") (pin "1") (pinfunction "1_1") (pintype "passive"))
      (node (ref "R80") (pin "1") (pinfunction "1_1") (pintype "passive"))
      (node (ref "R81") (pin "1") (pinfunction "1_1") (pintype "passive"))
      (node (ref "R82") (pin "1") (pinfunction "1_1") (pintype "passive"))
      (node (ref "R83") (pin "1") (pinfunction "1_1") (pintype "passive"))
      (node (ref "R84") (pin "1") (pinfunction "1_1") (pintype "passive"))
      (node (ref "R85") (pin "1") (pinfunction "1_1") (pintype "passive"))
      (node (ref "R86") (pin "1") (pinfunction "1_1") (pintype "passive"))
      (node (ref "U16") (pin "1") (pinfunction "AGND_2_1") (pintype "passive"))
      (node (ref "U16") (pin "20") (pinfunction "AGND_20") (pintype "passive"))
      (node (ref "U16") (pin "3") (pinfunction "AGND_3_3") (pintype "passive"))
      (node (ref "U16") (pin "4") (pinfunction "AGND_4_4") (pintype "passive"))
      (node (ref "U17") (pin "1") (pinfunction "AGND_2_1") (pintype "passive"))
      (node (ref "U17") (pin "15") (pinfunction "AS_15") (pintype "passive"))
      (node (ref "U17") (pin "20") (pinfunction "AGND_20") (pintype "passive"))
      (node (ref "U17") (pin "3") (pinfunction "AGND_3_3") (pintype "passive"))
      (node (ref "U17") (pin "4") (pinfunction "AGND_4_4") (pintype "passive"))
      (node (ref "U19") (pin "4") (pinfunction "V-_4") (pintype "passive"))
      (node (ref "U20") (pin "11") (pinfunction "ET3_11") (pintype "passive"))
      (node (ref "U20") (pin "13") (pinfunction "ET2_13") (pintype "passive"))
      (node (ref "U20") (pin "15") (pinfunction "ET1_15") (pintype "passive"))
      (node (ref "U20") (pin "2") (pinfunction "C1_2") (pintype "passive"))
      (node (ref "U20") (pin "4") (pinfunction "C2_4") (pintype "passive"))
      (node (ref "U20") (pin "6") (pinfunction "C3_6") (pintype "passive"))
      (node (ref "U20") (pin "8") (pinfunction "C4_8") (pintype "passive"))
      (node (ref "U20") (pin "9") (pinfunction "ET4_9") (pintype "passive"))
      (node (ref "U3") (pin "4") (pinfunction "V-_4") (pintype "passive"))
    )
    (net (code "20") (name "HEATER_OUT") (class "Default")
      (node (ref "J9") (pin "L4") (pinfunction "L4_L4") (pintype "passive"))
    )
    (net (code "21") (name "Ig_1") (class "Default")
      (node (ref "J9") (pin "M1") (pinfunction "M1_M1") (pintype "passive"))
    )
    (net (code "22") (name "Ig_2") (class "Default")
      (node (ref "J9") (pin "M2") (pinfunction "M2_M2") (pintype "passive"))
    )
    (net (code "23") (name "Ig_3") (class "Default")
      (node (ref "J9") (pin "M3") (pinfunction "M3_M3") (pintype "passive"))
    )
    (net (code "24") (name "Ig_4") (class "Default")
      (node (ref "J9") (pin "M4") (pinfunction "M4_M4") (pintype "passive"))
    )
    (net (code "25") (name "Injector_OUT_1") (class "Default")
      (node (ref "J9") (pin "A1") (pinfunction "A1_A1") (pintype "passive"))
    )
    (net (code "26") (name "Injector_OUT_2") (class "Default")
      (node (ref "J9") (pin "A4") (pinfunction "A4_A4") (pintype "passive"))
    )
    (net (code "27") (name "Injector_OUT_3") (class "Default")
      (node (ref "J9") (pin "A3") (pinfunction "A3_A3") (pintype "passive"))
    )
    (net (code "28") (name "Injector_OUT_4") (class "Default")
      (node (ref "J9") (pin "A2") (pinfunction "A2_A2") (pintype "passive"))
    )
    (net (code "29") (name "MAP_OUT") (class "Default")
      (node (ref "J9") (pin "K3") (pinfunction "K3_K3") (pintype "passive"))
    )
    (net (code "30") (name "Net-(R17-Pad1)") (class "Default")
      (node (ref "R17") (pin "1") (pinfunction "1_1") (pintype "passive"))
      (node (ref "R19") (pin "1") (pinfunction "1_1") (pintype "passive"))
      (node (ref "R60") (pin "2") (pinfunction "2_2") (pintype "passive"))
    )
    (net (code "31") (name "Net-(R62-Pad2)") (class "Default")
      (node (ref "R62") (pin "2") (pinfunction "2_2") (pintype "passive"))
      (node (ref "R75") (pin "1") (pinfunction "1_1") (pintype "passive"))
      (node (ref "R76") (pin "1") (pinfunction "1_1") (pintype "passive"))
    )
    (net (code "32") (name "Net-(R64-Pad2)") (class "Default")
      (node (ref "R64") (pin "2") (pinfunction "2_2") (pintype "passive"))
      (node (ref "R87") (pin "1") (pinfunction "1_1") (pintype "passive"))
      (node (ref "R88") (pin "1") (pinfunction "1_1") (pintype "passive"))
    )
    (net (code "33") (name "Net-(R108-Pad1)") (class "Default")
      (node (ref "R108") (pin "1") (pinfunction "1_1") (pintype "passive"))
      (node (ref "R109") (pin "1") (pinfunction "1_1") (pintype "passive"))
      (node (ref "R66") (pin "2") (pinfunction "2_2") (pintype "passive"))
    )
    (net (code "34") (name "Net-(R110-Pad1)") (class "Default")
      (node (ref "R110") (pin "1") (pinfunction "1_1") (pintype "passive"))
      (node (ref "R111") (pin "1") (pinfunction "1_1") (pintype "passive"))
      (node (ref "R112") (pin "2") (pinfunction "2_2") (pintype "passive"))
    )
    (net (code "35") (name "Net-(R114-Pad1)") (class "Default")
      (node (ref "R114") (pin "1") (pinfunction "1_1") (pintype "passive"))
      (node (ref "R115") (pin "1") (pinfunction "1_1") (pintype "passive"))
      (node (ref "R116") (pin "2") (pinfunction "2_2") (pintype "passive"))
    )
    (net (code "36") (name "Net-(U20-A1)") (class "Default")
      (node (ref "R53") (pin "2") (pinfunction "2_2") (pintype "passive"))
      (node (ref "U20") (pin "1") (pinfunction "A1_1") (pintype "passive"))
    )
    (net (code "37") (name "Net-(U20-A2)") (class "Default")
      (node (ref "R55") (pin "2") (pinfunction "2_2") (pintype "passive"))
      (node (ref "U20") (pin "3") (pinfunction "A2_3") (pintype "passive"))
    )
    (net (code "38") (name "Net-(U20-A3)") (class "Default")
      (node (ref "R57") (pin "2") (pinfunction "2_2") (pintype "passive"))
      (node (ref "U20") (pin "5") (pinfunction "A3_5") (pintype "passive"))
    )
    (net (code "39") (name "Net-(U20-A4)") (class "Default")
      (node (ref "R59") (pin "2") (pinfunction "2_2") (pintype "passive"))
      (node (ref "U20") (pin "7") (pinfunction "A4_7") (pintype "passive"))
    )
    (net (code "40") (name "PWM_MCU_OUT_1") (class "Default")
      (node (ref "J9") (pin "E4") (pinfunction "E4_E4") (pintype "passive"))
      (node (ref "Q3") (pin "2") (pinfunction "S_2") (pintype "passive"))
      (node (ref "R61") (pin "1") (pinfunction "1_1") (pintype "passive"))
    )
    (net (code "41") (name "PWM_MCU_OUT_2") (class "Default")
      (node (ref "J9") (pin "D4") (pinfunction "D4_D4") (pintype "passive"))
      (node (ref "Q10") (pin "2") (pinfunction "S_2") (pintype "passive"))
      (node (ref "R63") (pin "1") (pinfunction "1_1") (pintype "passive"))
    )
    (net (code "42") (name "PWM_MCU_OUT_3") (class "Default")
      (node (ref "J9") (pin "C4") (pinfunction "C4_C4") (pintype "passive"))
      (node (ref "Q11") (pin "2") (pinfunction "S_2") (pintype "passive"))
      (node (ref "R65") (pin "1") (pinfunction "1_1") (pintype "passive"))
    )
    (net (code "43") (name "PWM_MCU_OUT_4") (class "Default")
      (node (ref "J9") (pin "B4") (pinfunction "B4_B4") (pintype "passive"))
      (node (ref "Q12") (pin "2") (pinfunction "S_2") (pintype "passive"))
      (node (ref "R67") (pin "1") (pinfunction "1_1") (pintype "passive"))
    )
    (net (code "44") (name "PWM_MCU_OUT_5") (class "Default")
      (node (ref "J9") (pin "J2") (pinfunction "J2_J2") (pintype "passive"))
      (node (ref "Q14") (pin "2") (pinfunction "S_2") (pintype "passive"))
      (node (ref "R113") (pin "1") (pinfunction "1_1") (pintype "passive"))
    )
    (net (code "45") (name "PWM_MCU_OUT_6") (class "Default")
      (node (ref "J9") (pin "K2") (pinfunction "K2_K2") (pintype "passive"))
      (node (ref "Q15") (pin "2") (pinfunction "S_2") (pintype "passive"))
      (node (ref "R117") (pin "1") (pinfunction "1_1") (pintype "passive"))
    )
    (net (code "46") (name "PWM_OUT_1") (class "Default")
      (node (ref "Q3") (pin "3") (pinfunction "D_3") (pintype "passive"))
      (node (ref "R60") (pin "1") (pinfunction "1_1") (pintype "passive"))
    )
    (net (code "47") (name "PWM_OUT_2") (class "Default")
      (node (ref "Q10") (pin "3") (pinfunction "D_3") (pintype "passive"))
      (node (ref "R62") (pin "1") (pinfunction "1_1") (pintype "passive"))
    )
    (net (code "48") (name "PWM_OUT_3") (class "Default")
      (node (ref "Q11") (pin "3") (pinfunction "D_3") (pintype "passive"))
      (node (ref "R64") (pin "1") (pinfunction "1_1") (pintype "passive"))
    )
    (net (code "49") (name "PWM_OUT_4") (class "Default")
      (node (ref "Q12") (pin "3") (pinfunction "D_3") (pintype "passive"))
      (node (ref "R66") (pin "1") (pinfunction "1_1") (pintype "passive"))
    )
    (net (code "50") (name "PWM_OUT_5") (class "Default")
      (node (ref "Q14") (pin "3") (pinfunction "D_3") (pintype "passive"))
      (node (ref "R112") (pin "1") (pinfunction "1_1") (pintype "passive"))
    )
    (net (code "51") (name "PWM_OUT_6") (class "Default")
      (node (ref "Q15") (pin "3") (pinfunction "D_3") (pintype "passive"))
      (node (ref "R116") (pin "1") (pinfunction "1_1") (pintype "passive"))
    )
    (net (code "52") (name "SCL_2") (class "Default")
      (node (ref "U16") (pin "19") (pinfunction "SCL_19") (pintype "passive"))
      (node (ref "U17") (pin "19") (pinfunction "SCL_19") (pintype "passive"))
    )
    (net (code "53") (name "SDA_2") (class "Default")
      (node (ref "U16") (pin "18") (pinfunction "SDA_18") (pintype "passive"))
      (node (ref "U17") (pin "18") (pinfunction "SDA_18") (pintype "passive"))
    )
    (net (code "54") (name "Sensor_1") (class "Default")
      (node (ref "C45") (pin "2") (pinfunction "2_2") (pintype "passive"))
      (node (ref "J9") (pin "B1") (pinfunction "B1_B1") (pintype "passive"))
      (node (ref "R44") (pin "2") (pinfunction "2_2") (pintype "passive"))
      (node (ref "R46") (pin "2") (pinfunction "2_2") (pintype "passive"))
      (node (ref "U3") (pin "7") (pinfunction "IN_7") (pintype "input"))
    )
    (net (code "55") (name "Sensor_2") (class "Default")
      (node (ref "C46") (pin "2") (pinfunction "2_2") (pintype "passive"))
      (node (ref "J9") (pin "C1") (pinfunction "C1_C1") (pintype "passive"))
      (node (ref "R45") (pin "2") (pinfunction "2_2") (pintype "passive"))
      (node (ref "R47") (pin "2") (pinfunction "2_2") (pintype "passive"))
      (node (ref "U3") (pin "6") (pinfunction "IN_6_6") (pintype "input"))
    )
    (net (code "56") (name "Sensor_3") (class "Default")
      (node (ref "C44") (pin "2") (pinfunction "2_2") (pintype "passive"))
      (node (ref "J9") (pin "D1") (pinfunction "D1_D1") (pintype "passive"))
      (node (ref "R43") (pin "2") (pinfunction "2_2") (pintype "passive"))
      (node (ref "R48") (pin "2") (pinfunction "2_2") (pintype "passive"))
      (node (ref "U3") (pin "5") (pinfunction "IN_4_5") (pintype "input"))
    )
    (net (code "57") (name "Sensor_4") (class "Default")
      (node (ref "C48") (pin "2") (pinfunction "2_2") (pintype "passive"))
      (node (ref "J9") (pin "E1") (pinfunction "E1_E1") (pintype "passive"))
      (node (ref "R50") (pin "2") (pinfunction "2_2") (pintype "passive"))
      (node (ref "R68") (pin "2") (pinfunction "2_2") (pintype "passive"))
      (node (ref "U19") (pin "3") (pinfunction "IN_5_3") (pintype "input"))
    )
    (net (code "58") (name "Sensor_5") (class "Default")
      (node (ref "C49") (pin "2") (pinfunction "2_2") (pintype "passive"))
      (node (ref "J9") (pin "F1") (pinfunction "F1_F1") (pintype "passive"))
      (node (ref "R51") (pin "2") (pinfunction "2_2") (pintype "passive"))
      (node (ref "R69") (pin "2") (pinfunction "2_2") (pintype "passive"))
      (node (ref "U19") (pin "2") (pinfunction "IN_3_2") (pintype "input"))
    )
    (net (code "59") (name "Sensor_6") (class "Default")
      (node (ref "C47") (pin "2") (pinfunction "2_2") (pintype "passive"))
      (node (ref "J9") (pin "G1") (pinfunction "G1_G1") (pintype "passive"))
      (node (ref "R49") (pin "2") (pinfunction "2_2") (pintype "passive"))
      (node (ref "R70") (pin "2") (pinfunction "2_2") (pintype "passive"))
      (node (ref "U19") (pin "1") (pinfunction "IN_2_1") (pintype "input"))
    )
    (net (code "60") (name "Sensor_7") (class "Default")
      (node (ref "C7") (pin "2") (pinfunction "2_2") (pintype "passive"))
      (node (ref "J9") (pin "H1") (pinfunction "H1_H1") (pintype "passive"))
      (node (ref "R10") (pin "2") (pinfunction "2_2") (pintype "passive"))
      (node (ref "R71") (pin "2") (pinfunction "2_2") (pintype "passive"))
      (node (ref "U3") (pin "1") (pinfunction "IN_2_1") (pintype "input"))
    )
    (net (code "61") (name "Sensor_8") (class "Default")
      (node (ref "C8") (pin "2") (pinfunction "2_2") (pintype "passive"))
      (node (ref "J9") (pin "J1") (pinfunction "J1_J1") (pintype "passive"))
      (node (ref "R11") (pin "2") (pinfunction "2_2") (pintype "passive"))
      (node (ref "R72") (pin "2") (pinfunction "2_2") (pintype "passive"))
      (node (ref "U3") (pin "2") (pinfunction "IN_3_2") (pintype "input"))
    )
    (net (code "62") (name "Sensor_9") (class "Default")
      (node (ref "C6") (pin "2") (pinfunction "2_2") (pintype "passive"))
      (node (ref "J9") (pin "K1") (pinfunction "K1_K1") (pintype "passive"))
      (node (ref "R73") (pin "2") (pinfunction "2_2") (pintype "passive"))
      (node (ref "R9") (pin "2") (pinfunction "2_2") (pintype "passive"))
      (node (ref "U3") (pin "3") (pinfunction "IN_5_3") (pintype "input"))
    )
    (net (code "63") (name "Sensor_10") (class "Default")
      (node (ref "C10") (pin "2") (pinfunction "2_2") (pintype "passive"))
      (node (ref "J9") (pin "H2") (pinfunction "H2_H2") (pintype "passive"))
      (node (ref "R18") (pin "2") (pinfunction "2_2") (pintype "passive"))
      (node (ref "R74") (pin "2") (pinfunction "2_2") (pintype "passive"))
      (node (ref "U19") (pin "5") (pinfunction "IN_4_5") (pintype "input"))
    )
    (net (code "64") (name "Sensor_OPT_0") (class "Default")
      (node (ref "R53") (pin "1") (pinfunction "1_1") (pintype "passive"))
    )
    (net (code "65") (name "Sensor_OPT_0_OUT") (class "Default")
      (node (ref "J9") (pin "L3") (pinfunction "L3_L3") (pintype "passive"))
      (node (ref "R52") (pin "1") (pinfunction "1_1") (pintype "passive"))
      (node (ref "U17") (pin "10") (pinfunction "VIN7_10") (pintype "passive"))
      (node (ref "U20") (pin "16") (pinfunction "CT1_16") (pintype "passive"))
    )
    (net (code "66") (name "Sensor_OPT_1") (class "Default")
      (node (ref "R55") (pin "1") (pinfunction "1_1") (pintype "passive"))
    )
    (net (code "67") (name "Sensor_OPT_1_OUT") (class "Default")
      (node (ref "J9") (pin "L2") (pinfunction "L2_L2") (pintype "passive"))
      (node (ref "R54") (pin "1") (pinfunction "1_1") (pintype "passive"))
      (node (ref "U17") (pin "11") (pinfunction "VIN8_11") (pintype "passive"))
      (node (ref "U20") (pin "14") (pinfunction "CT2_14") (pintype "passive"))
    )
    (net (code "68") (name "Sensor_OPT_2") (class "Default")
      (node (ref "R57") (pin "1") (pinfunction "1_1") (pintype "passive"))
    )
    (net (code "69") (name "Sensor_OPT_2_OUT") (class "Default")
      (node (ref "J9") (pin "L1") (pinfunction "L1_L1") (pintype "passive"))
      (node (ref "R56") (pin "1") (pinfunction "1_1") (pintype "passive"))
      (node (ref "U16") (pin "10") (pinfunction "VIN7_10") (pintype "passive"))
      (node (ref "U20") (pin "12") (pinfunction "CT3_12") (pintype "passive"))
    )
    (net (code "70") (name "Sensor_OPT_3") (class "Default")
      (node (ref "R59") (pin "1") (pinfunction "1_1") (pintype "passive"))
    )
    (net (code "71") (name "Sensor_OPT_3_OUT") (class "Default")
      (node (ref "J9") (pin "K4") (pinfunction "K4_K4") (pintype "passive"))
      (node (ref "R58") (pin "1") (pinfunction "1_1") (pintype "passive"))
      (node (ref "U16") (pin "11") (pinfunction "VIN8_11") (pintype "passive"))
      (node (ref "U20") (pin "10") (pinfunction "CT4_10") (pintype "passive"))
    )
    (net (code "72") (name "Sensor_OUT_1") (class "Default")
      (node (ref "R46") (pin "1") (pinfunction "1_1") (pintype "passive"))
      (node (ref "R77") (pin "2") (pinfunction "2_2") (pintype "passive"))
      (node (ref "U16") (pin "14") (pinfunction "VIN2_14") (pintype "passive"))
    )
    (net (code "73") (name "Sensor_OUT_2") (class "Default")
      (node (ref "R47") (pin "1") (pinfunction "1_1") (pintype "passive"))
      (node (ref "R78") (pin "2") (pinfunction "2_2") (pintype "passive"))
      (node (ref "U16") (pin "13") (pinfunction "VIN4_13") (pintype "passive"))
    )
    (net (code "74") (name "Sensor_OUT_3") (class "Default")
      (node (ref "R48") (pin "1") (pinfunction "1_1") (pintype "passive"))
      (node (ref "R79") (pin "2") (pinfunction "2_2") (pintype "passive"))
      (node (ref "U16") (pin "12") (pinfunction "VIN6_12") (pintype "passive"))
    )
    (net (code "75") (name "Sensor_OUT_4") (class "Default")
      (node (ref "R68") (pin "1") (pinfunction "1_1") (pintype "passive"))
      (node (ref "R80") (pin "2") (pinfunction "2_2") (pintype "passive"))
      (node (ref "U17") (pin "14") (pinfunction "VIN2_14") (pintype "passive"))
    )
    (net (code "76") (name "Sensor_OUT_5") (class "Default")
      (node (ref "R69") (pin "1") (pinfunction "1_1") (pintype "passive"))
      (node (ref "R81") (pin "2") (pinfunction "2_2") (pintype "passive"))
      (node (ref "U17") (pin "13") (pinfunction "VIN4_13") (pintype "passive"))
    )
    (net (code "77") (name "Sensor_OUT_6") (class "Default")
      (node (ref "R70") (pin "1") (pinfunction "1_1") (pintype "passive"))
      (node (ref "R82") (pin "2") (pinfunction "2_2") (pintype "passive"))
      (node (ref "U17") (pin "12") (pinfunction "VIN6_12") (pintype "passive"))
    )
    (net (code "78") (name "Sensor_OUT_7") (class "Default")
      (node (ref "R71") (pin "1") (pinfunction "1_1") (pintype "passive"))
      (node (ref "R83") (pin "2") (pinfunction "2_2") (pintype "passive"))
      (node (ref "U16") (pin "7") (pinfunction "VIN1_7") (pintype "passive"))
    )
    (net (code "79") (name "Sensor_OUT_8") (class "Default")
      (node (ref "R72") (pin "1") (pinfunction "1_1") (pintype "passive"))
      (node (ref "R84") (pin "2") (pinfunction "2_2") (pintype "passive"))
      (node (ref "U16") (pin "8") (pinfunction "VIN3_8") (pintype "passive"))
    )
    (net (code "80") (name "Sensor_OUT_9") (class "Default")
      (node (ref "R73") (pin "1") (pinfunction "1_1") (pintype "passive"))
      (node (ref "R85") (pin "2") (pinfunction "2_2") (pintype "passive"))
      (node (ref "U16") (pin "9") (pinfunction "VIN5_9") (pintype "passive"))
    )
    (net (code "81") (name "Sensor_OUT_10") (class "Default")
      (node (ref "R74") (pin "1") (pinfunction "1_1") (pintype "passive"))
      (node (ref "R86") (pin "2") (pinfunction "2_2") (pintype "passive"))
      (node (ref "U17") (pin "7") (pinfunction "VIN1_7") (pintype "passive"))
    )
    (net (code "82") (name "TVS_11") (class "Default")
      (node (ref "U19") (pin "6") (pinfunction "IN_6_6") (pintype "input"))
    )
    (net (code "83") (name "TVS_12") (class "Default")
      (node (ref "U19") (pin "7") (pinfunction "IN_7") (pintype "input"))
    )
    (net (code "84") (name "VIN") (class "Default")
      (node (ref "R109") (pin "2") (pinfunction "2_2") (pintype "passive"))
      (node (ref "R111") (pin "2") (pinfunction "2_2") (pintype "passive"))
      (node (ref "R115") (pin "2") (pinfunction "2_2") (pintype "passive"))
      (node (ref "R19") (pin "2") (pinfunction "2_2") (pintype "passive"))
      (node (ref "R76") (pin "2") (pinfunction "2_2") (pintype "passive"))
      (node (ref "R88") (pin "2") (pinfunction "2_2") (pintype "passive"))
    )
    (net (code "85") (name "unconnected-(U16-ALERT{slash}BUSY-Pad17)") (class "Default")
      (node (ref "U16") (pin "17") (pinfunction "ALERT/BUSY_17") (pintype "passive"))
    )
    (net (code "86") (name "unconnected-(U16-CONVST*-Pad16)") (class "Default")
      (node (ref "U16") (pin "16") (pinfunction "CONVST*_16") (pintype "passive"))
    )
    (net (code "87") (name "unconnected-(U16-REFIN-Pad6)") (class "Default")
      (node (ref "U16") (pin "6") (pinfunction "REFIN_6") (pintype "passive"))
    )
    (net (code "88") (name "unconnected-(U17-ALERT{slash}BUSY-Pad17)") (class "Default")
      (node (ref "U17") (pin "17") (pinfunction "ALERT/BUSY_17") (pintype "passive"))
    )
    (net (code "89") (name "unconnected-(U17-CONVST*-Pad16)") (class "Default")
      (node (ref "U17") (pin "16") (pinfunction "CONVST*_16") (pintype "passive"))
    )
    (net (code "90") (name "unconnected-(U17-REFIN-Pad6)") (class "Default")
      (node (ref "U17") (pin "6") (pinfunction "REFIN_6") (pintype "passive"))
    )
    (net (code "91") (name "unconnected-(U17-VIN3-Pad8)") (class "Default")
      (node (ref "U17") (pin "8") (pinfunction "VIN3_8") (pintype "passive"))
    )
    (net (code "92") (name "unconnected-(U17-VIN5-Pad9)") (class "Default")
      (node (ref "U17") (pin "9") (pinfunction "VIN5_9") (pintype "passive"))
    )
  )
)
